# 13.net
KiCad netlist of a schematic drawn in Altium Designer
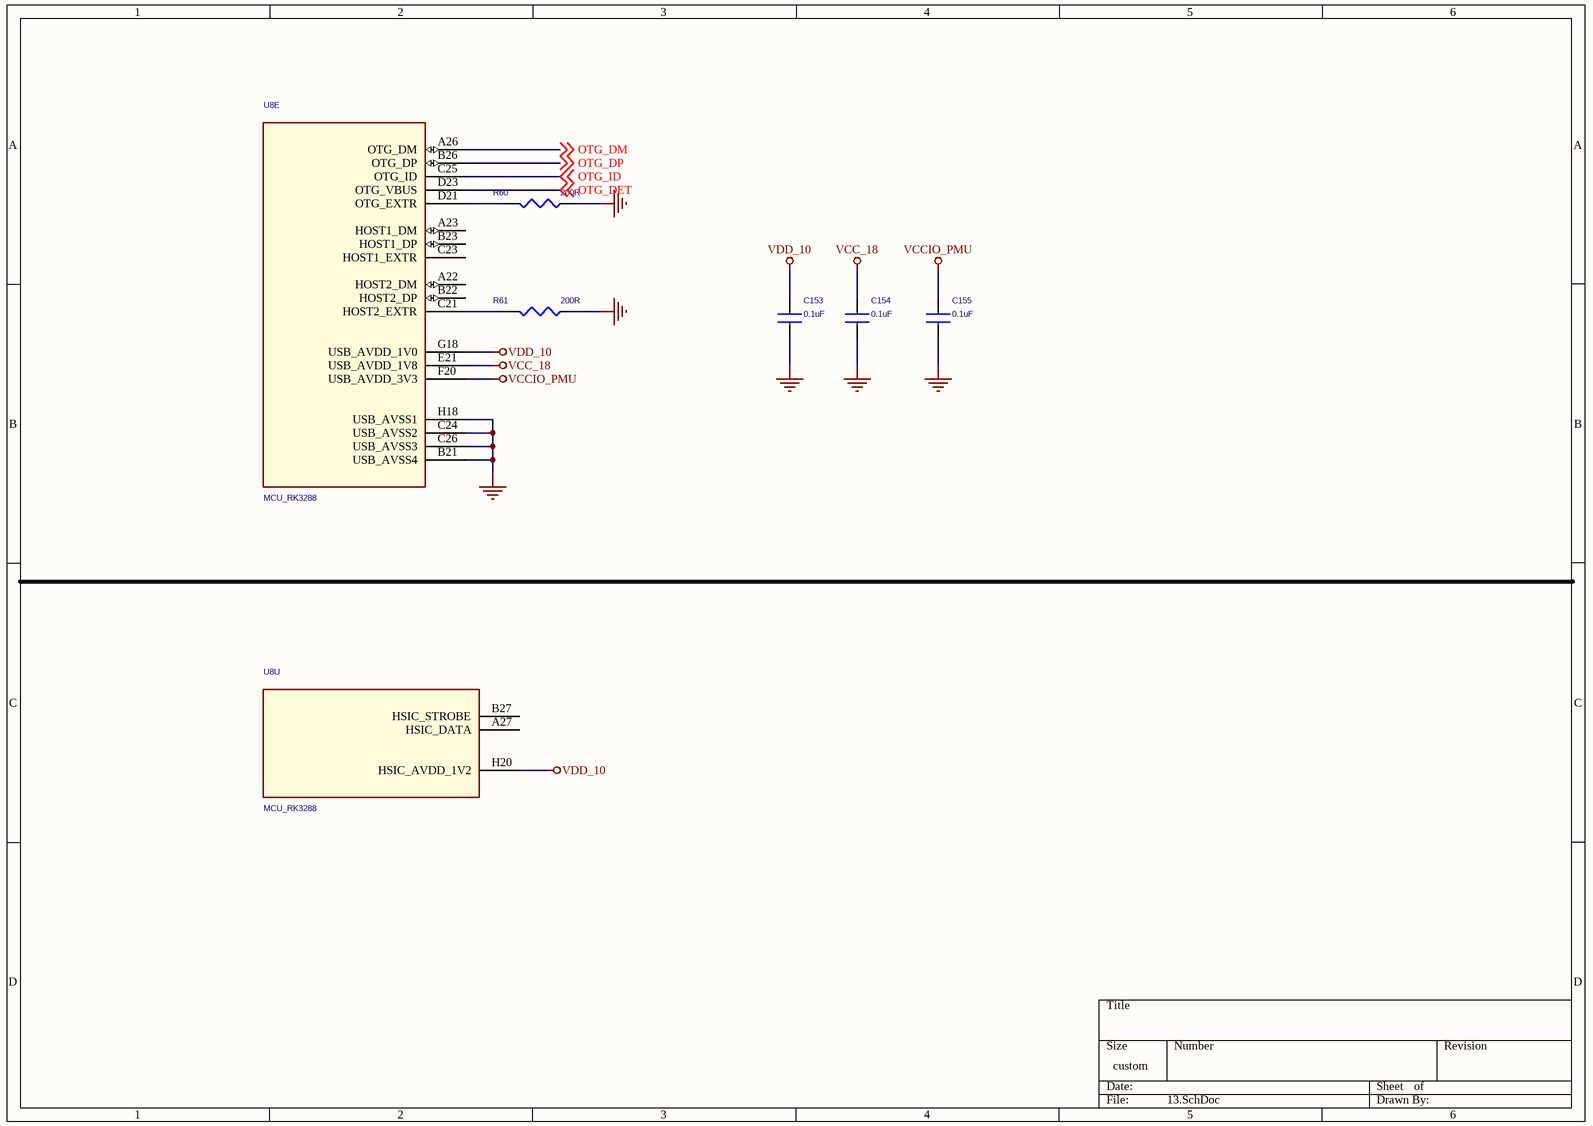
[diagram p0: 13.SchDoc]

(export (version "E")
  (design (tool "Eeschema 10.0.6"))
  (components
    (comp (ref "C153")
      (value "0.1uF")
      (footprint "C0603")
      (description "贴片电容")
      (libsource (lib "*") (part "CAP NP_Dup3"))
    )
    (comp (ref "C154")
      (value "0.1uF")
      (footprint "C0603")
      (description "贴片电容")
      (libsource (lib "*") (part "CAP NP_Dup3"))
    )
    (comp (ref "C155")
      (value "0.1uF")
      (footprint "C0603")
      (description "贴片电容")
      (libsource (lib "*") (part "CAP NP_Dup3"))
    )
    (comp (ref "R60") (value "200R") (footprint "r0402") (libsource (lib "*") (part "RESISTOR_1_Dup2")))
    (comp (ref "R61") (value "200R") (footprint "r0402") (libsource (lib "*") (part "RESISTOR_1_Dup2")))
    (comp (ref "U8")
      (value "MCU_RK3288")
      (footprint "BGA453-19X19")
      (libsource (lib "*") (part "MCU_RK3288_3"))
    )
  )
  (nets
    (net (code "1") (name "GND") (class "Default")
      (node (ref "C153") (pin "1") (pinfunction "1_1") (pintype "passive"))
      (node (ref "C154") (pin "1") (pinfunction "1_1") (pintype "passive"))
      (node (ref "C155") (pin "1") (pinfunction "1_1") (pintype "passive"))
      (node (ref "R60") (pin "1") (pinfunction "1_1") (pintype "passive"))
      (node (ref "R61") (pin "1") (pinfunction "1_1") (pintype "passive"))
      (node (ref "U8") (pin "B21") (pinfunction "USB_AVSS4_B21") (pintype "power_in"))
      (node (ref "U8") (pin "C24") (pinfunction "USB_AVSS2_C24") (pintype "power_in"))
      (node (ref "U8") (pin "C26") (pinfunction "USB_AVSS3_C26") (pintype "power_in"))
      (node (ref "U8") (pin "H18") (pinfunction "USB_AVSS1_H18") (pintype "power_in"))
    )
    (net (code "2") (name "Net-(U8E-HOST2_EXTR)") (class "Default")
      (node (ref "R61") (pin "2") (pinfunction "2_2") (pintype "passive"))
      (node (ref "U8") (pin "C21") (pinfunction "HOST2_EXTR_C21") (pintype "passive"))
    )
    (net (code "3") (name "Net-(U8E-OTG_EXTR)") (class "Default")
      (node (ref "R60") (pin "2") (pinfunction "2_2") (pintype "passive"))
      (node (ref "U8") (pin "D21") (pinfunction "OTG_EXTR_D21") (pintype "passive"))
    )
    (net (code "4") (name "OTG_DET") (class "Default")
      (node (ref "U8") (pin "D23") (pinfunction "OTG_VBUS_D23") (pintype "passive"))
    )
    (net (code "5") (name "OTG_DM") (class "Default")
      (node (ref "U8") (pin "A26") (pinfunction "OTG_DM_A26") (pintype "bidirectional"))
    )
    (net (code "6") (name "OTG_DP") (class "Default")
      (node (ref "U8") (pin "B26") (pinfunction "OTG_DP_B26") (pintype "bidirectional"))
    )
    (net (code "7") (name "OTG_ID") (class "Default")
      (node (ref "U8") (pin "C25") (pinfunction "OTG_ID_C25") (pintype "passive"))
    )
    (net (code "8") (name "VCCIO_PMU") (class "Default")
      (node (ref "C155") (pin "2") (pinfunction "2_2") (pintype "passive"))
      (node (ref "U8") (pin "F20") (pinfunction "USB_AVDD_3V3_F20") (pintype "power_in"))
    )
    (net (code "9") (name "VCC_18") (class "Default")
      (node (ref "C154") (pin "2") (pinfunction "2_2") (pintype "passive"))
      (node (ref "U8") (pin "E21") (pinfunction "USB_AVDD_1V8_E21") (pintype "power_in"))
    )
    (net (code "10") (name "VDD_10") (class "Default")
      (node (ref "C153") (pin "2") (pinfunction "2_2") (pintype "passive"))
      (node (ref "U8") (pin "G18") (pinfunction "USB_AVDD_1V0_G18") (pintype "power_in"))
      (node (ref "U8") (pin "H20") (pinfunction "HSIC_AVDD_1V2_H20") (pintype "power_in"))
    )
    (net (code "11") (name "unconnected-(U8E-HOST1_DM-PadA23)") (class "Default")
      (node (ref "U8") (pin "A23") (pinfunction "HOST1_DM_A23") (pintype "bidirectional"))
    )
    (net (code "12") (name "unconnected-(U8E-HOST1_DP-PadB23)") (class "Default")
      (node (ref "U8") (pin "B23") (pinfunction "HOST1_DP_B23") (pintype "bidirectional"))
    )
    (net (code "13") (name "unconnected-(U8E-HOST1_EXTR-PadC23)") (class "Default")
      (node (ref "U8") (pin "C23") (pinfunction "HOST1_EXTR_C23") (pintype "passive"))
    )
    (net (code "14") (name "unconnected-(U8E-HOST2_DM-PadA22)") (class "Default")
      (node (ref "U8") (pin "A22") (pinfunction "HOST2_DM_A22") (pintype "bidirectional"))
    )
    (net (code "15") (name "unconnected-(U8E-HOST2_DP-PadB22)") (class "Default")
      (node (ref "U8") (pin "B22") (pinfunction "HOST2_DP_B22") (pintype "bidirectional"))
    )
    (net (code "16") (name "unconnected-(U8U-HSIC_DATA-PadA27)") (class "Default")
      (node (ref "U8") (pin "A27") (pinfunction "HSIC_DATA_A27") (pintype "passive"))
    )
    (net (code "17") (name "unconnected-(U8U-HSIC_STROBE-PadB27)") (class "Default")
      (node (ref "U8") (pin "B27") (pinfunction "HSIC_STROBE_B27") (pintype "passive"))
    )
  )
)
